# CH32X035F8U-R0.net
KiCad netlist of a schematic drawn in Altium Designer
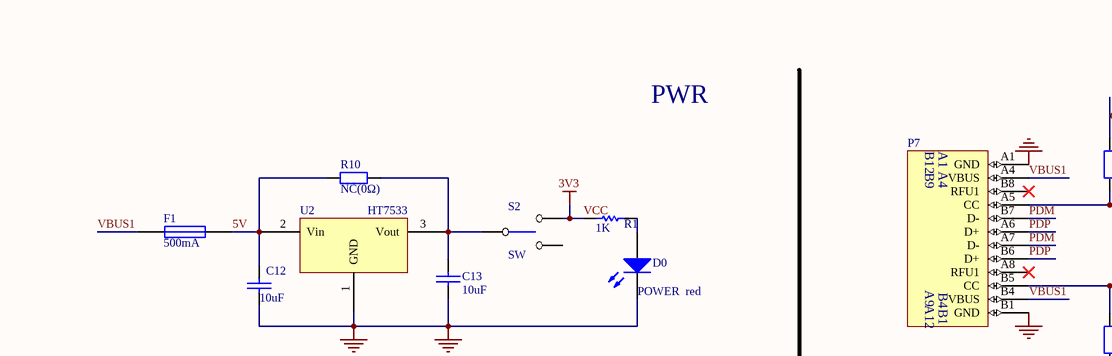
[diagram p0: CH32X035F8U-R0.SchDoc, top left]
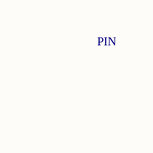
[diagram p1: CH32X035F8U-R0.SchDoc, top right]
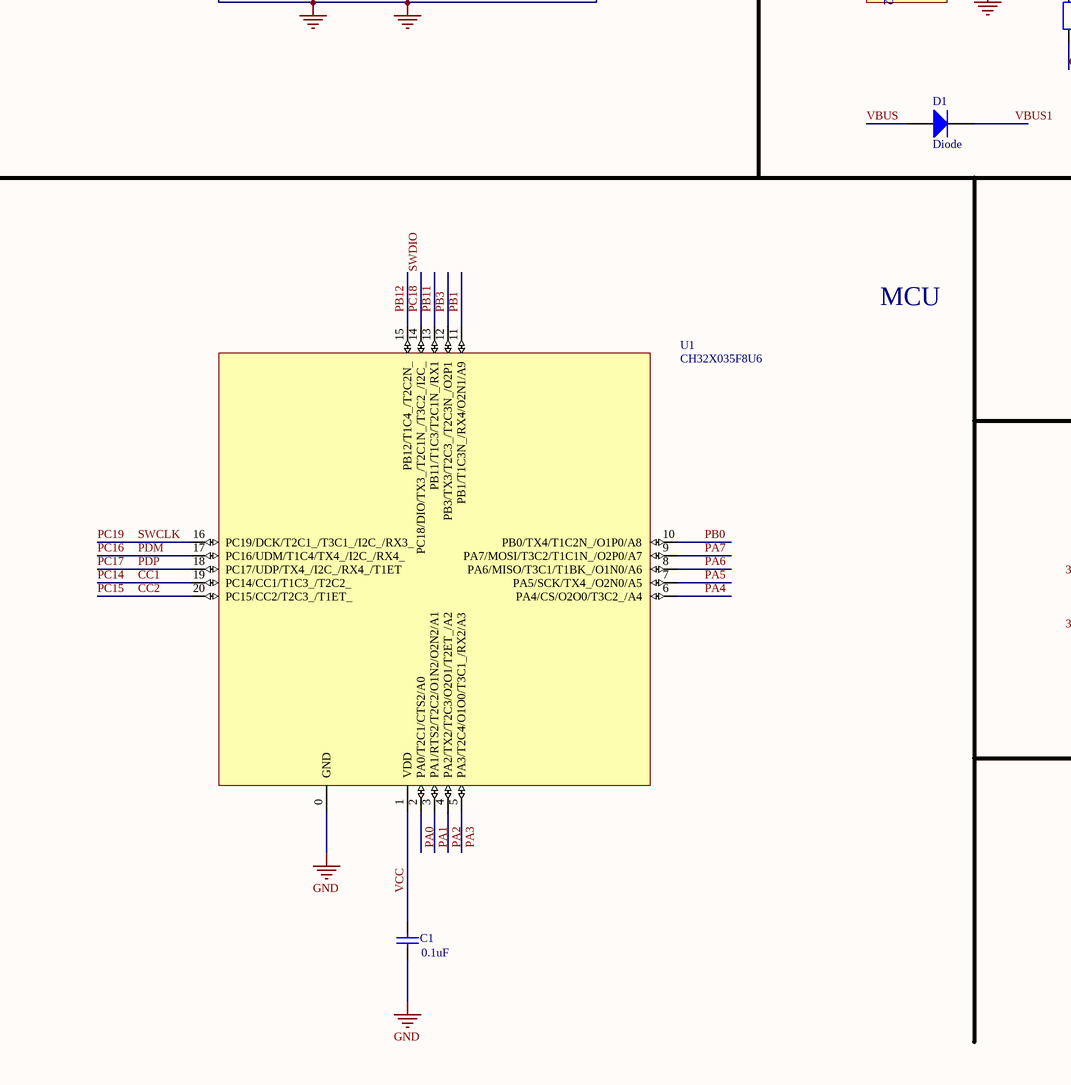
[diagram p2: CH32X035F8U-R0.SchDoc, bottom left]
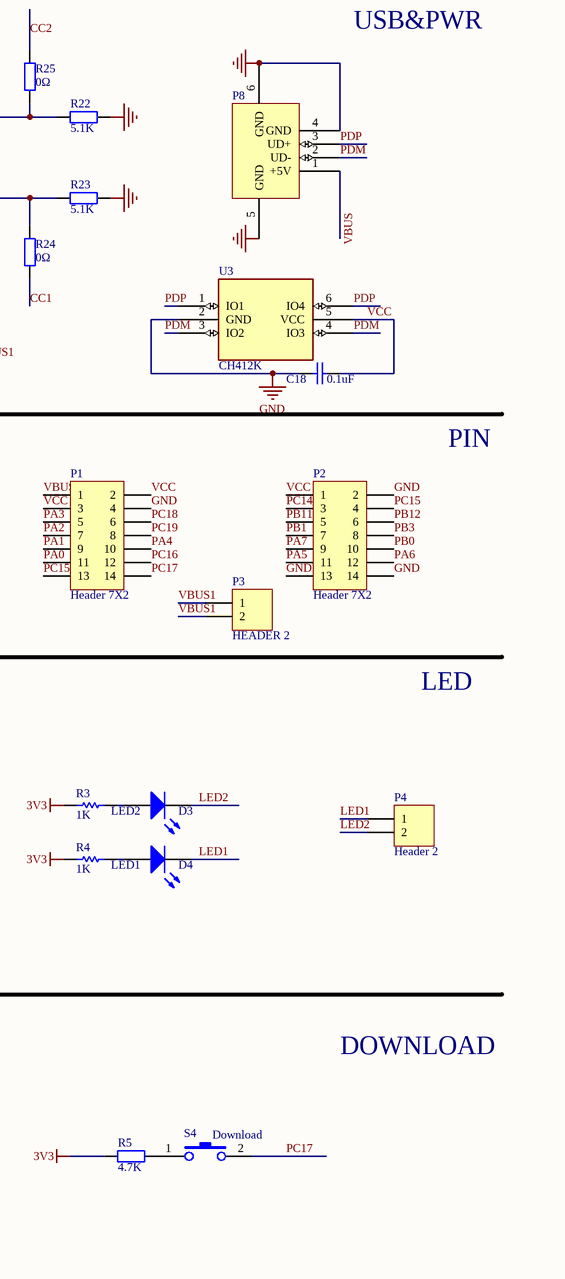
[diagram p3: CH32X035F8U-R0.SchDoc, bottom right]

(export (version "E")
  (design (tool "Eeschema 10.0.6"))
  (components
    (comp (ref "C1")
      (value "0.1uF")
      (footprint "0603_C")
      (description "Capacitor")
      (libsource (lib "Miscellaneous Devices") (part "Cap"))
    )
    (comp (ref "C12")
      (value "10uF")
      (footprint "0603_C")
      (description "Capacitor")
      (libsource (lib "*") (part "CAP"))
    )
    (comp (ref "C13")
      (value "10uF")
      (footprint "0603_C")
      (description "Capacitor")
      (libsource (lib "*") (part "CAP"))
    )
    (comp (ref "C18")
      (value "0.1uF")
      (footprint "0603_C")
      (description "Capacitor")
      (libsource (lib "Miscellaneous Devices") (part "Cap"))
    )
    (comp (ref "D0")
      (value "POWER  red")
      (footprint "0603+")
      (description "Typical INFRARED GaAs LED")
      (fields (field (name "PUBLISHER") "Altium Limited"))
      (libsource (lib "*") (part "LED0"))
    )
    (comp (ref "D1")
      (value "Diode")
      (footprint "SOD-123")
      (description "Default Diode")
      (fields (field (name "PUBLISHER") "Altium Limited"))
      (libsource (lib "Miscellaneous Devices") (part "Diode"))
    )
    (comp (ref "D3")
      (value "LED2")
      (footprint "0603+")
      (description "Typical INFRARED GaAs LED")
      (fields (field (name "PUBLISHER") "Altium Limited"))
      (libsource (lib "*") (part "LED0"))
    )
    (comp (ref "D4")
      (value "LED1")
      (footprint "0603+")
      (description "Typical INFRARED GaAs LED")
      (fields (field (name "PUBLISHER") "Altium Limited"))
      (libsource (lib "*") (part "LED0"))
    )
    (comp (ref "F1")
      (value "500mA")
      (footprint "0603")
      (description "Fuse")
      (libsource (lib "*") (part "FUSE1"))
    )
    (comp (ref "P1")
      (value "Header 7X2")
      (footprint "IDC14-2.54mm")
      (description "Header, 7-Pin, Dual row")
      (fields (field (name "PUBLISHER") "Altium Limited"))
      (libsource (lib "Miscellaneous Connectors") (part "Header 7X2"))
    )
    (comp (ref "P2")
      (value "Header 7X2")
      (footprint "IDC14-2.54mm")
      (description "Header, 7-Pin, Dual row")
      (fields (field (name "PUBLISHER") "Altium Limited"))
      (libsource (lib "Miscellaneous Connectors") (part "Header 7X2"))
    )
    (comp (ref "P3")
      (value "HEADER 2")
      (footprint "MYPCB:SIP2-2.54mm")
      (description "Header, 2-Pin")
      (libsource (lib "wch_sch_others") (part "HEADER 2"))
    )
    (comp (ref "P4")
      (value "Header 2")
      (footprint "SIP2-2.54mm")
      (description "Header, 2-Pin")
      (fields (field (name "PUBLISHER") "Altium Limited"))
      (libsource (lib "Miscellaneous Connectors") (part "Header 2"))
    )
    (comp (ref "P7")
      (value "TYPE-C")
      (footprint "TYPE-C-Receptacle-2.0")
      (libsource (lib "*") (part "TYPE-C1"))
    )
    (comp (ref "P8")
      (value "USB_A")
      (footprint "USBAF")
      (description "USB Port")
      (libsource (lib "*") (part "USB"))
    )
    (comp (ref "R1")
      (value "1K")
      (footprint "0603")
      (description "Semiconductor Resistor")
      (fields (field (name "PUBLISHER") "Altium Limited"))
      (libsource (lib "*") (part "Res Semi"))
    )
    (comp (ref "R3")
      (value "1K")
      (footprint "0603")
      (description "Semiconductor Resistor")
      (fields (field (name "PUBLISHER") "Altium Limited"))
      (libsource (lib "*") (part "Res Semi"))
    )
    (comp (ref "R4")
      (value "1K")
      (footprint "0603")
      (description "Semiconductor Resistor")
      (fields (field (name "PUBLISHER") "Altium Limited"))
      (libsource (lib "*") (part "Res Semi"))
    )
    (comp (ref "R5")
      (value "4.7K")
      (footprint "0603")
      (description "Resistor")
      (libsource (lib "") (part "Res2_1"))
    )
    (comp (ref "R10")
      (value "NC(0Ω)")
      (footprint "0603")
      (description "Resistor")
      (fields (field (name "PUBLISHER") "Altium Limited"))
      (libsource (lib "*") (part "Res2"))
    )
    (comp (ref "R22")
      (value "5.1K")
      (footprint "0603")
      (description "Resistor")
      (libsource (lib "") (part "Res2_1"))
    )
    (comp (ref "R23")
      (value "5.1K")
      (footprint "0603")
      (description "Resistor")
      (libsource (lib "") (part "Res2_1"))
    )
    (comp (ref "R24")
      (value "0Ω")
      (footprint "0603")
      (description "Resistor")
      (libsource (lib "Miscellaneous Devices") (part "Res2"))
    )
    (comp (ref "R25")
      (value "0Ω")
      (footprint "0603")
      (description "Resistor")
      (libsource (lib "Miscellaneous Devices") (part "Res2"))
    )
    (comp (ref "S2") (value "SW") (footprint "SW1") (libsource (lib "*") (part "SW")))
    (comp (ref "S4")
      (value "Download")
      (footprint "SMD_6.1x3.65x2.5mm-KEY")
      (libsource (lib "wch_sch_others") (part "KEY1"))
    )
    (comp (ref "U1")
      (value "CH32X035F8U6")
      (footprint "QFN20_3X3")
      (description "RISC-V MCU with USB/PD/ADC/SPI/I2C/UART/OA")
      (libsource (lib "DHXXXSCH") (part "CH32X035F8U6"))
    )
    (comp (ref "U2")
      (value "HT7533")
      (footprint "SOT-89")
      (libsource (lib "wch_sch_others") (part "1117-3.3V"))
    )
    (comp (ref "U3")
      (value "CH412K")
      (footprint "SOT-363")
      (description "Qaud ESD protect, high speed")
      (libsource (lib "CHXXX") (part "CH412K"))
    )
  )
  (nets
    (net (code "1") (name "/5V") (class "Default")
      (node (ref "C12") (pin "1") (pinfunction "1_1") (pintype "passive"))
      (node (ref "F1") (pin "2") (pinfunction "2_2") (pintype "passive"))
      (node (ref "R10") (pin "2") (pinfunction "2_2") (pintype "passive"))
      (node (ref "U2") (pin "2") (pinfunction "Vin_2") (pintype "passive"))
    )
    (net (code "3") (name "/CC1") (class "Default")
      (node (ref "P2") (pin "3") (pinfunction "3_3") (pintype "passive"))
      (node (ref "R24") (pin "1") (pinfunction "1_1") (pintype "passive"))
      (node (ref "U1") (pin "19") (pinfunction "PC14/CC1/T1C3_/T2C2__19") (pintype "bidirectional"))
    )
    (net (code "4") (name "/CC2") (class "Default")
      (node (ref "P1") (pin "13") (pinfunction "13_13") (pintype "passive"))
      (node (ref "P2") (pin "4") (pinfunction "4_4") (pintype "passive"))
      (node (ref "R25") (pin "2") (pinfunction "2_2") (pintype "passive"))
      (node (ref "U1") (pin "20") (pinfunction "PC15/CC2/T2C3_/T1ET__20") (pintype "bidirectional"))
    )
    (net (code "5") (name "/LED1") (class "Default")
      (node (ref "D4") (pin "2") (pinfunction "K_2") (pintype "passive"))
      (node (ref "P4") (pin "1") (pinfunction "1_1") (pintype "passive"))
    )
    (net (code "6") (name "/LED2") (class "Default")
      (node (ref "D3") (pin "2") (pinfunction "K_2") (pintype "passive"))
      (node (ref "P4") (pin "2") (pinfunction "2_2") (pintype "passive"))
    )
    (net (code "7") (name "/PA0") (class "Default")
      (node (ref "P1") (pin "11") (pinfunction "11_11") (pintype "passive"))
      (node (ref "U1") (pin "2") (pinfunction "PA0/T2C1/CTS2/A0_2") (pintype "bidirectional"))
    )
    (net (code "8") (name "/PA1") (class "Default")
      (node (ref "P1") (pin "9") (pinfunction "9_9") (pintype "passive"))
      (node (ref "U1") (pin "3") (pinfunction "PA1/RTS2/T2C2/O1N2/O2N2/A1_3") (pintype "bidirectional"))
    )
    (net (code "9") (name "/PA2") (class "Default")
      (node (ref "P1") (pin "7") (pinfunction "7_7") (pintype "passive"))
      (node (ref "U1") (pin "4") (pinfunction "PA2/TX2/T2C3/O2O1/T2ET_/A2_4") (pintype "bidirectional"))
    )
    (net (code "10") (name "/PA3") (class "Default")
      (node (ref "P1") (pin "5") (pinfunction "5_5") (pintype "passive"))
      (node (ref "U1") (pin "5") (pinfunction "PA3/T2C4/O1O0/T3C1_/RX2/A3_5") (pintype "bidirectional"))
    )
    (net (code "11") (name "/PA4") (class "Default")
      (node (ref "P1") (pin "10") (pinfunction "10_10") (pintype "passive"))
      (node (ref "U1") (pin "6") (pinfunction "PA4/CS/O2O0/T3C2_/A4_6") (pintype "bidirectional"))
    )
    (net (code "12") (name "/PA5") (class "Default")
      (node (ref "P2") (pin "11") (pinfunction "11_11") (pintype "passive"))
      (node (ref "U1") (pin "7") (pinfunction "PA5/SCK/TX4_/O2N0/A5_7") (pintype "bidirectional"))
    )
    (net (code "13") (name "/PA6") (class "Default")
      (node (ref "P2") (pin "12") (pinfunction "12_12") (pintype "passive"))
      (node (ref "U1") (pin "8") (pinfunction "PA6/MISO/T3C1/T1BK_/O1N0/A6_8") (pintype "bidirectional"))
    )
    (net (code "14") (name "/PA7") (class "Default")
      (node (ref "P2") (pin "9") (pinfunction "9_9") (pintype "passive"))
      (node (ref "U1") (pin "9") (pinfunction "PA7/MOSI/T3C2/T1C1N_/O2P0/A7_9") (pintype "bidirectional"))
    )
    (net (code "15") (name "/PB0") (class "Default")
      (node (ref "P2") (pin "10") (pinfunction "10_10") (pintype "passive"))
      (node (ref "U1") (pin "10") (pinfunction "PB0/TX4/T1C2N_/O1P0/A8_10") (pintype "bidirectional"))
    )
    (net (code "16") (name "/PB1") (class "Default")
      (node (ref "P2") (pin "7") (pinfunction "7_7") (pintype "passive"))
      (node (ref "U1") (pin "11") (pinfunction "PB1/T1C3N_/RX4/O2N1/A9_11") (pintype "bidirectional"))
    )
    (net (code "17") (name "/PB3") (class "Default")
      (node (ref "P2") (pin "8") (pinfunction "8_8") (pintype "passive"))
      (node (ref "U1") (pin "12") (pinfunction "PB3/TX3/T2C3_/T2C3N_/O2P1_12") (pintype "bidirectional"))
    )
    (net (code "18") (name "/PB11") (class "Default")
      (node (ref "P2") (pin "5") (pinfunction "5_5") (pintype "passive"))
      (node (ref "U1") (pin "13") (pinfunction "PB11/T1C3/T2C1N_/RX1_13") (pintype "bidirectional"))
    )
    (net (code "19") (name "/PB12") (class "Default")
      (node (ref "P2") (pin "6") (pinfunction "6_6") (pintype "passive"))
      (node (ref "U1") (pin "15") (pinfunction "PB12/T1C4_/T2C2N__15") (pintype "bidirectional"))
    )
    (net (code "20") (name "/PC16") (class "Default")
      (node (ref "P1") (pin "12") (pinfunction "12_12") (pintype "passive"))
      (node (ref "P7") (pin "A7") (pinfunction "D-_A7") (pintype "bidirectional"))
      (node (ref "P7") (pin "B7") (pinfunction "D-_B7") (pintype "bidirectional"))
      (node (ref "P8") (pin "2") (pinfunction "UD-_2") (pintype "bidirectional"))
      (node (ref "U1") (pin "17") (pinfunction "PC16/UDM/T1C4/TX4_/I2C_/RX4__17") (pintype "bidirectional"))
      (node (ref "U3") (pin "3") (pinfunction "IO2_3") (pintype "bidirectional"))
      (node (ref "U3") (pin "4") (pinfunction "IO3_4") (pintype "bidirectional"))
    )
    (net (code "21") (name "/PC17") (class "Default")
      (node (ref "P1") (pin "14") (pinfunction "14_14") (pintype "passive"))
      (node (ref "P7") (pin "A6") (pinfunction "D+_A6") (pintype "bidirectional"))
      (node (ref "P7") (pin "B6") (pinfunction "D+_B6") (pintype "bidirectional"))
      (node (ref "P8") (pin "3") (pinfunction "UD+_3") (pintype "bidirectional"))
      (node (ref "S4") (pin "2") (pinfunction "2_2") (pintype "passive"))
      (node (ref "U1") (pin "18") (pinfunction "PC17/UDP/TX4_/I2C_/RX4_/T1ET_18") (pintype "bidirectional"))
      (node (ref "U3") (pin "1") (pinfunction "IO1_1") (pintype "bidirectional"))
      (node (ref "U3") (pin "6") (pinfunction "IO4_6") (pintype "bidirectional"))
    )
    (net (code "22") (name "/PC18") (class "Default")
      (node (ref "P1") (pin "6") (pinfunction "6_6") (pintype "passive"))
      (node (ref "U1") (pin "14") (pinfunction "PC18/DIO/TX3_/T2C1N_/T3C2_/I2C__14") (pintype "bidirectional"))
    )
    (net (code "23") (name "/PC19") (class "Default")
      (node (ref "P1") (pin "8") (pinfunction "8_8") (pintype "passive"))
      (node (ref "U1") (pin "16") (pinfunction "PC19/DCK/T2C1_/T3C1_/I2C_/RX3__16") (pintype "bidirectional"))
    )
    (net (code "24") (name "/VBUS") (class "Default")
      (node (ref "D1") (pin "1") (pinfunction "A_1") (pintype "passive"))
      (node (ref "P1") (pin "1") (pinfunction "1_1") (pintype "passive"))
      (node (ref "P8") (pin "1") (pinfunction "+5V_1") (pintype "power_in"))
    )
    (net (code "25") (name "/VBUS1") (class "Default")
      (node (ref "D1") (pin "2") (pinfunction "K_2") (pintype "passive"))
      (node (ref "F1") (pin "1") (pinfunction "1_1") (pintype "passive"))
      (node (ref "P3") (pin "1") (pinfunction "1_1") (pintype "passive"))
      (node (ref "P3") (pin "2") (pinfunction "2_2") (pintype "passive"))
      (node (ref "P7") (pin "A4") (pinfunction "VBUS_A4") (pintype "bidirectional"))
      (node (ref "P7") (pin "B4") (pinfunction "VBUS_B4") (pintype "bidirectional"))
    )
    (net (code "26") (name "3V3") (class "Default")
      (node (ref "C1") (pin "2") (pinfunction "2_2") (pintype "passive"))
      (node (ref "C18") (pin "2") (pinfunction "2_2") (pintype "passive"))
      (node (ref "P1") (pin "2") (pinfunction "2_2") (pintype "passive"))
      (node (ref "P1") (pin "3") (pinfunction "3_3") (pintype "passive"))
      (node (ref "P2") (pin "1") (pinfunction "1_1") (pintype "passive"))
      (node (ref "R1") (pin "2") (pinfunction "2_2") (pintype "passive"))
      (node (ref "R3") (pin "1") (pinfunction "1_1") (pintype "passive"))
      (node (ref "R4") (pin "1") (pinfunction "1_1") (pintype "passive"))
      (node (ref "R5") (pin "1") (pinfunction "1_1") (pintype "passive"))
      (node (ref "S2") (pin "3") (pinfunction "3_3") (pintype "passive"))
      (node (ref "U1") (pin "1") (pinfunction "VDD_1") (pintype "power_in"))
      (node (ref "U3") (pin "5") (pinfunction "VCC_5") (pintype "power_in"))
    )
    (net (code "27") (name "GND") (class "Default")
      (node (ref "C1") (pin "1") (pinfunction "1_1") (pintype "passive"))
      (node (ref "C12") (pin "2") (pinfunction "2_2") (pintype "passive"))
      (node (ref "C13") (pin "2") (pinfunction "2_2") (pintype "passive"))
      (node (ref "C18") (pin "1") (pinfunction "1_1") (pintype "passive"))
      (node (ref "D0") (pin "2") (pinfunction "K_2") (pintype "passive"))
      (node (ref "P1") (pin "4") (pinfunction "4_4") (pintype "passive"))
      (node (ref "P2") (pin "13") (pinfunction "13_13") (pintype "passive"))
      (node (ref "P2") (pin "14") (pinfunction "14_14") (pintype "passive"))
      (node (ref "P2") (pin "2") (pinfunction "2_2") (pintype "passive"))
      (node (ref "P7") (pin "A1") (pinfunction "GND_A1") (pintype "bidirectional"))
      (node (ref "P7") (pin "B1") (pinfunction "GND_B1") (pintype "bidirectional"))
      (node (ref "P8") (pin "4") (pinfunction "GND_4") (pintype "power_in"))
      (node (ref "P8") (pin "5") (pinfunction "GND_5") (pintype "power_in"))
      (node (ref "P8") (pin "6") (pinfunction "GND_6") (pintype "power_in"))
      (node (ref "R22") (pin "2") (pinfunction "2_2") (pintype "passive"))
      (node (ref "R23") (pin "2") (pinfunction "2_2") (pintype "passive"))
      (node (ref "U1") (pin "0") (pinfunction "GND_0") (pintype "power_in"))
      (node (ref "U2") (pin "1") (pinfunction "GND_1") (pintype "passive"))
      (node (ref "U3") (pin "2") (pinfunction "GND_2") (pintype "power_in"))
    )
    (net (code "28") (name "Net-(D0-A)") (class "Default")
      (node (ref "D0") (pin "1") (pinfunction "A_1") (pintype "passive"))
      (node (ref "R1") (pin "1") (pinfunction "1_1") (pintype "passive"))
    )
    (net (code "29") (name "Net-(D3-A)") (class "Default")
      (node (ref "D3") (pin "1") (pinfunction "A_1") (pintype "passive"))
      (node (ref "R3") (pin "2") (pinfunction "2_2") (pintype "passive"))
    )
    (net (code "30") (name "Net-(D4-A)") (class "Default")
      (node (ref "D4") (pin "1") (pinfunction "A_1") (pintype "passive"))
      (node (ref "R4") (pin "2") (pinfunction "2_2") (pintype "passive"))
    )
    (net (code "31") (name "Net-(P7-CC-PadA5)") (class "Default")
      (node (ref "P7") (pin "A5") (pinfunction "CC_A5") (pintype "bidirectional"))
      (node (ref "R22") (pin "1") (pinfunction "1_1") (pintype "passive"))
      (node (ref "R25") (pin "1") (pinfunction "1_1") (pintype "passive"))
    )
    (net (code "32") (name "Net-(P7-CC-PadB5)") (class "Default")
      (node (ref "P7") (pin "B5") (pinfunction "CC_B5") (pintype "bidirectional"))
      (node (ref "R23") (pin "1") (pinfunction "1_1") (pintype "passive"))
      (node (ref "R24") (pin "2") (pinfunction "2_2") (pintype "passive"))
    )
    (net (code "33") (name "Net-(R5-Pad2)") (class "Default")
      (node (ref "R5") (pin "2") (pinfunction "2_2") (pintype "passive"))
      (node (ref "S4") (pin "1") (pinfunction "1_1") (pintype "passive"))
    )
    (net (code "34") (name "Net-(U2-Vout)") (class "Default")
      (node (ref "C13") (pin "1") (pinfunction "1_1") (pintype "passive"))
      (node (ref "R10") (pin "1") (pinfunction "1_1") (pintype "passive"))
      (node (ref "S2") (pin "1") (pinfunction "1_1") (pintype "passive"))
      (node (ref "U2") (pin "3") (pinfunction "Vout_3") (pintype "passive"))
    )
    (net (code "35") (name "unconnected-(P7-RFU1-PadA8)") (class "Default")
      (node (ref "P7") (pin "A8") (pinfunction "RFU1_A8") (pintype "bidirectional+no_connect"))
    )
    (net (code "36") (name "unconnected-(P7-RFU1-PadB8)") (class "Default")
      (node (ref "P7") (pin "B8") (pinfunction "RFU1_B8") (pintype "bidirectional+no_connect"))
    )
    (net (code "37") (name "unconnected-(S2-Pad2)") (class "Default")
      (node (ref "S2") (pin "2") (pinfunction "2_2") (pintype "passive"))
    )
  )
)
